# T04_Schematic.net
KiCad netlist of a schematic drawn in EAGLE
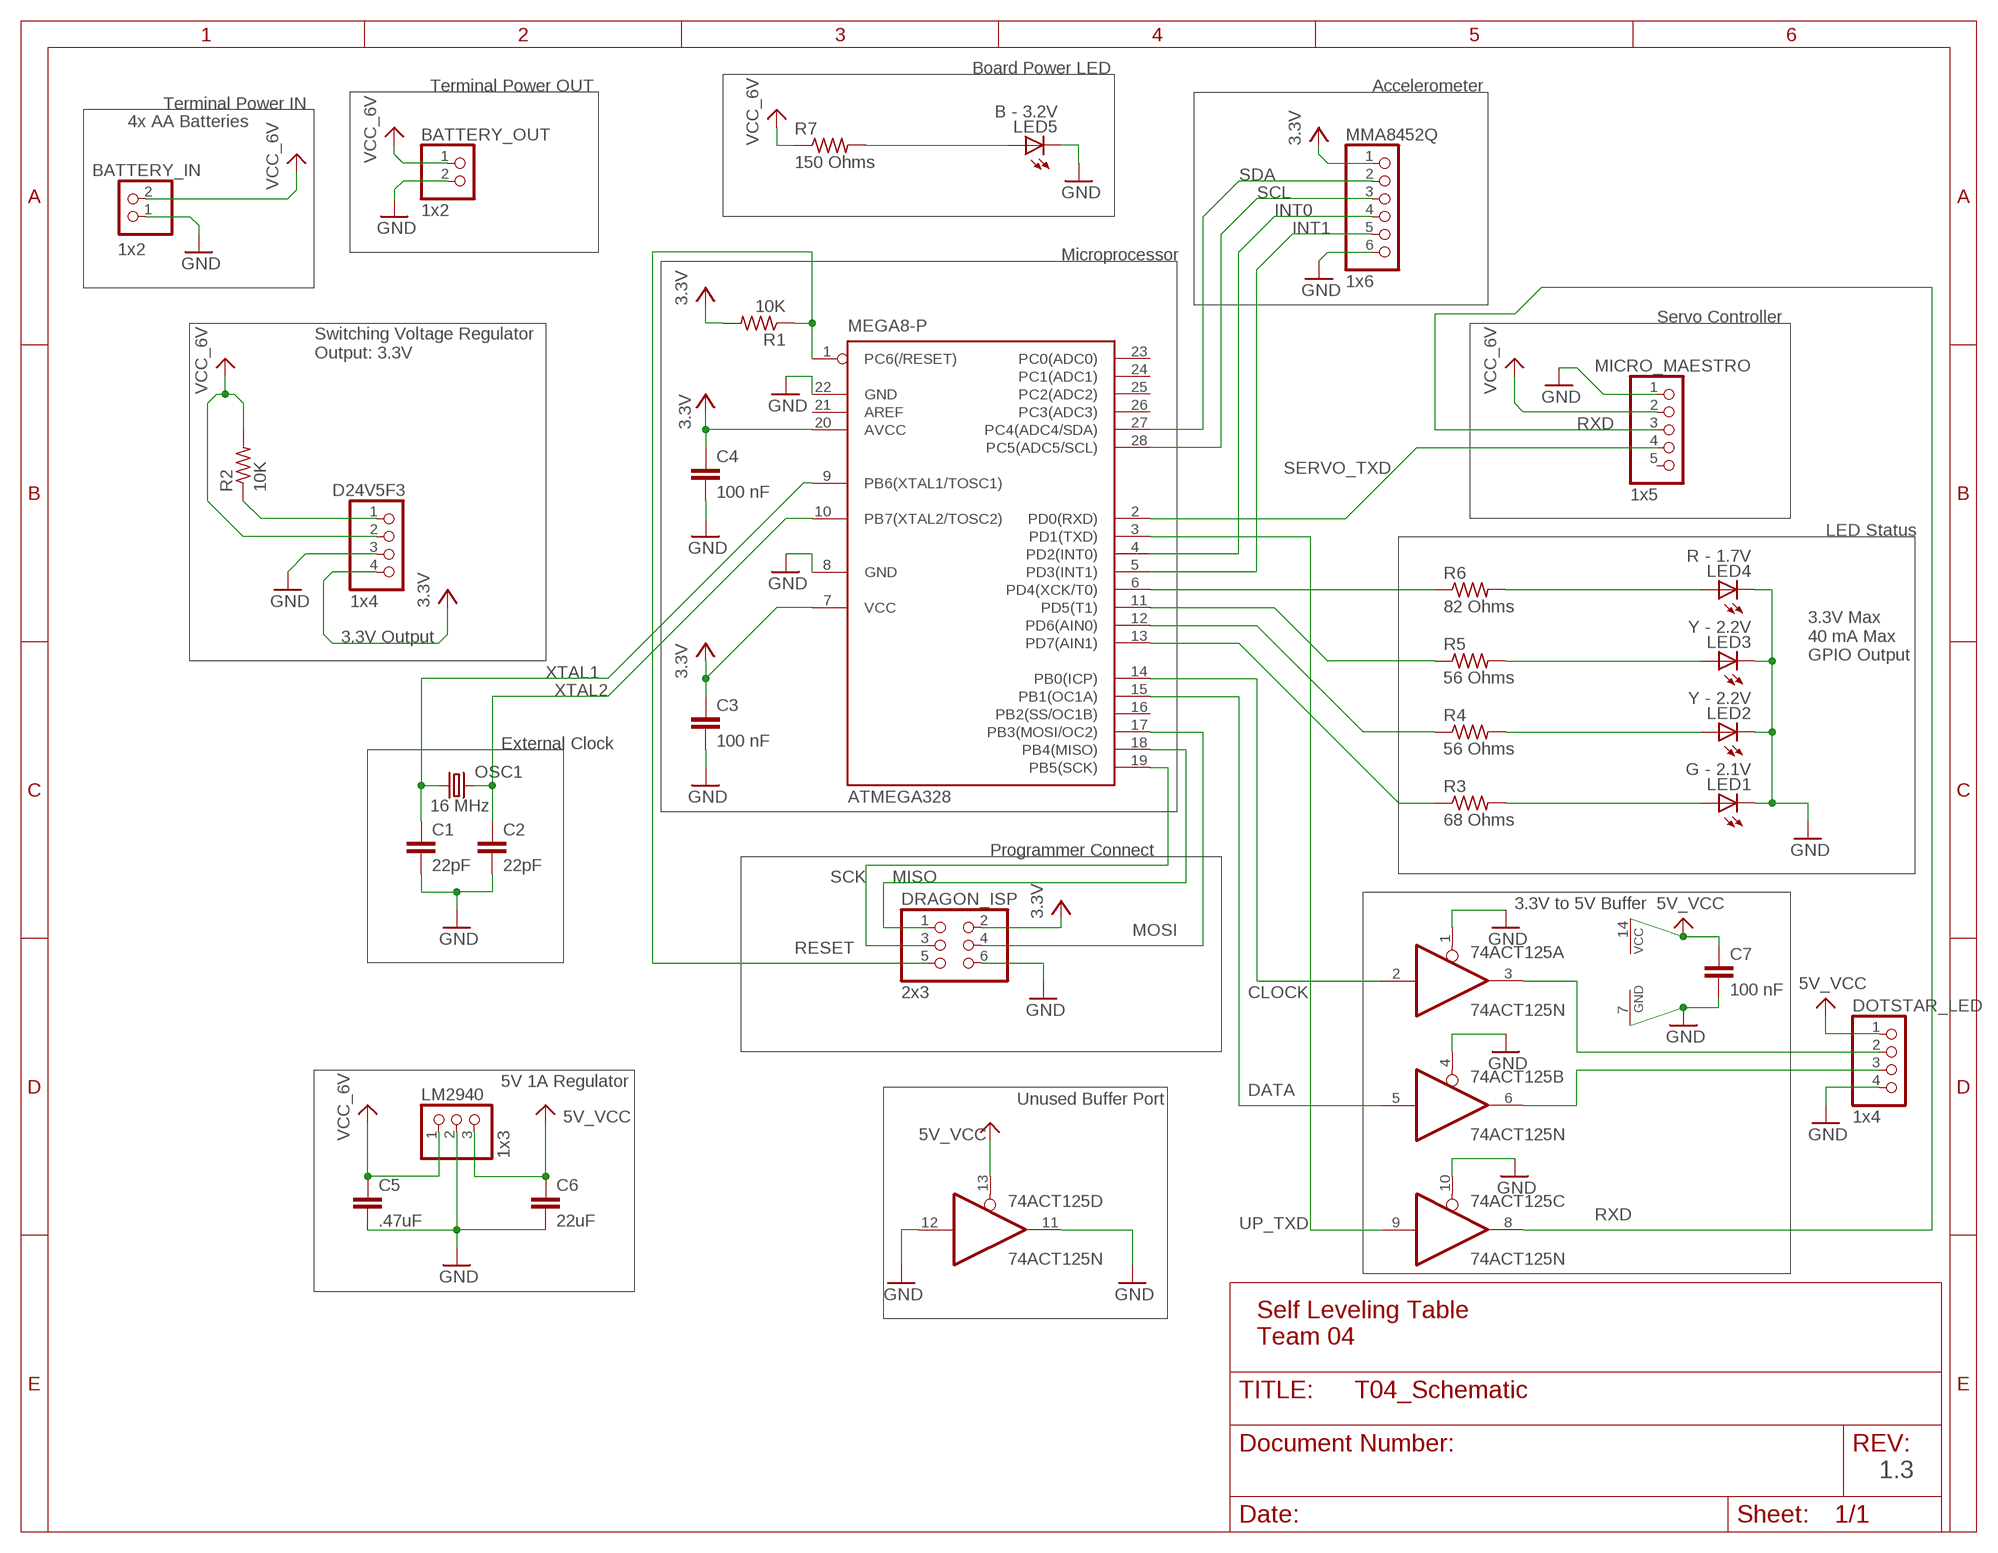
[diagram p0: schematic, sheet 1]

(export (version "E")
  (design (tool "Eeschema 10.0.6"))
  (components
    (comp (ref "74ACT125")
      (value "74ACT125N")
      (footprint "eagle-import:DIL14")
      (libsource (lib "eagle-import") (part "74125NACT"))
    )
    (comp (ref "ATMEGA328")
      (value "MEGA8-P")
      (footprint "eagle-import:DIL28-3")
      (libsource (lib "eagle-import") (part "MEGA8-P"))
    )
    (comp (ref "BATTERY_IN")
      (value "1x2")
      (footprint "eagle-import:1X02")
      (libsource (lib "eagle-import") (part "PINHD-1X2"))
    )
    (comp (ref "BATTERY_OUT")
      (value "1x2")
      (footprint "eagle-import:1X02")
      (libsource (lib "eagle-import") (part "PINHD-1X2"))
    )
    (comp (ref "C1")
      (value "22pF")
      (footprint "eagle-import:C1206")
      (libsource (lib "eagle-import") (part "C-EUC1206"))
    )
    (comp (ref "C2")
      (value "22pF")
      (footprint "eagle-import:C1206")
      (libsource (lib "eagle-import") (part "C-EUC1206"))
    )
    (comp (ref "C3")
      (value "100 nF")
      (footprint "eagle-import:C1206")
      (libsource (lib "eagle-import") (part "C-EUC1206"))
    )
    (comp (ref "C4")
      (value "100 nF")
      (footprint "eagle-import:C1206")
      (libsource (lib "eagle-import") (part "C-EUC1206"))
    )
    (comp (ref "C5")
      (value ".47uF")
      (footprint "eagle-import:C1206")
      (libsource (lib "eagle-import") (part "C-EUC1206"))
    )
    (comp (ref "C6")
      (value "22uF")
      (footprint "eagle-import:C1206")
      (libsource (lib "eagle-import") (part "C-EUC1206"))
    )
    (comp (ref "C7")
      (value "100 nF")
      (footprint "eagle-import:C1206")
      (libsource (lib "eagle-import") (part "C-EUC1206"))
    )
    (comp (ref "D24V5F3")
      (value "1x4")
      (footprint "eagle-import:1X04")
      (libsource (lib "eagle-import") (part "PINHD-1X4"))
    )
    (comp (ref "DOTSTAR_LED")
      (value "1x4")
      (footprint "eagle-import:1X04")
      (libsource (lib "eagle-import") (part "PINHD-1X4"))
    )
    (comp (ref "DRAGON_ISP")
      (value "2x3")
      (footprint "eagle-import:2X03")
      (libsource (lib "eagle-import") (part "PINHD-2X3"))
    )
    (comp (ref "LED1")
      (value "G - 2.1V")
      (footprint "eagle-import:1206")
      (libsource (lib "eagle-import") (part "LEDSMT1206"))
    )
    (comp (ref "LED2")
      (value "Y - 2.2V")
      (footprint "eagle-import:1206")
      (libsource (lib "eagle-import") (part "LEDSMT1206"))
    )
    (comp (ref "LED3")
      (value "Y - 2.2V")
      (footprint "eagle-import:1206")
      (libsource (lib "eagle-import") (part "LEDSMT1206"))
    )
    (comp (ref "LED4")
      (value "R - 1.7V")
      (footprint "eagle-import:1206")
      (libsource (lib "eagle-import") (part "LEDSMT1206"))
    )
    (comp (ref "LED5")
      (value "B - 3.2V")
      (footprint "eagle-import:1206")
      (libsource (lib "eagle-import") (part "LEDSMT1206"))
    )
    (comp (ref "LM2940")
      (value "1x3")
      (footprint "eagle-import:1X03")
      (libsource (lib "eagle-import") (part "PINHD-1X3"))
    )
    (comp (ref "MICRO_MAESTRO")
      (value "1x5")
      (footprint "eagle-import:1X05")
      (libsource (lib "eagle-import") (part "PINHD-1X5"))
    )
    (comp (ref "MMA8452Q")
      (value "1x6")
      (footprint "eagle-import:1X06")
      (libsource (lib "eagle-import") (part "PINHD-1X6"))
    )
    (comp (ref "OSC1")
      (value "16 MHz")
      (footprint "eagle-import:HC49US")
      (libsource (lib "eagle-import") (part "CRYSTALHC49US"))
    )
    (comp (ref "R1")
      (value "10K")
      (footprint "eagle-import:M1206")
      (libsource (lib "eagle-import") (part "R-US_M1206"))
    )
    (comp (ref "R2")
      (value "10K")
      (footprint "eagle-import:M1206")
      (libsource (lib "eagle-import") (part "R-US_M1206"))
    )
    (comp (ref "R3")
      (value "68 Ohms")
      (footprint "eagle-import:R1206")
      (libsource (lib "eagle-import") (part "R-US_R1206"))
    )
    (comp (ref "R4")
      (value "56 Ohms")
      (footprint "eagle-import:R1206")
      (libsource (lib "eagle-import") (part "R-US_R1206"))
    )
    (comp (ref "R5")
      (value "56 Ohms")
      (footprint "eagle-import:R1206")
      (libsource (lib "eagle-import") (part "R-US_R1206"))
    )
    (comp (ref "R6")
      (value "82 Ohms")
      (footprint "eagle-import:R1206")
      (libsource (lib "eagle-import") (part "R-US_R1206"))
    )
    (comp (ref "R7")
      (value "150 Ohms")
      (footprint "eagle-import:R1206")
      (libsource (lib "eagle-import") (part "R-US_R1206"))
    )
  )
  (nets
    (net (code "1") (name "/CLOCK") (class "Default")
      (node (ref "74ACT125") (pin "2") (pinfunction "I_2") (pintype "input"))
      (node (ref "ATMEGA328") (pin "14") (pinfunction "PB0(ICP)_14") (pintype "bidirectional"))
    )
    (net (code "2") (name "/DATA") (class "Default")
      (node (ref "74ACT125") (pin "5") (pinfunction "I_5") (pintype "input"))
      (node (ref "ATMEGA328") (pin "15") (pinfunction "PB1(OC1A)_15") (pintype "bidirectional"))
    )
    (net (code "3") (name "/INT0") (class "Default")
      (node (ref "ATMEGA328") (pin "4") (pinfunction "PD2(INT0)_4") (pintype "bidirectional"))
      (node (ref "MMA8452Q") (pin "4") (pinfunction "4_4") (pintype "passive"))
    )
    (net (code "4") (name "/INT1") (class "Default")
      (node (ref "ATMEGA328") (pin "5") (pinfunction "PD3(INT1)_5") (pintype "bidirectional"))
      (node (ref "MMA8452Q") (pin "5") (pinfunction "5_5") (pintype "passive"))
    )
    (net (code "5") (name "/MISO") (class "Default")
      (node (ref "ATMEGA328") (pin "18") (pinfunction "PB4(MISO)_18") (pintype "bidirectional"))
      (node (ref "DRAGON_ISP") (pin "1") (pinfunction "1_1") (pintype "passive"))
    )
    (net (code "6") (name "/MOSI") (class "Default")
      (node (ref "ATMEGA328") (pin "17") (pinfunction "PB3(MOSI/OC2)_17") (pintype "bidirectional"))
      (node (ref "DRAGON_ISP") (pin "4") (pinfunction "4_4") (pintype "passive"))
    )
    (net (code "7") (name "/RESET") (class "Default")
      (node (ref "ATMEGA328") (pin "1") (pinfunction "PC6(/RESET)_1") (pintype "bidirectional"))
      (node (ref "DRAGON_ISP") (pin "5") (pinfunction "5_5") (pintype "passive"))
      (node (ref "R1") (pin "1") (pinfunction "1_1") (pintype "passive"))
    )
    (net (code "8") (name "/RXD") (class "Default")
      (node (ref "74ACT125") (pin "8") (pinfunction "O_8") (pintype "tri_state"))
      (node (ref "MICRO_MAESTRO") (pin "3") (pinfunction "3_3") (pintype "passive"))
    )
    (net (code "9") (name "/SCK") (class "Default")
      (node (ref "ATMEGA328") (pin "19") (pinfunction "PB5(SCK)_19") (pintype "bidirectional"))
      (node (ref "DRAGON_ISP") (pin "3") (pinfunction "3_3") (pintype "passive"))
    )
    (net (code "10") (name "/SCL") (class "Default")
      (node (ref "ATMEGA328") (pin "28") (pinfunction "PC5(ADC5/SCL)_28") (pintype "bidirectional"))
      (node (ref "MMA8452Q") (pin "3") (pinfunction "3_3") (pintype "passive"))
    )
    (net (code "11") (name "/SDA") (class "Default")
      (node (ref "ATMEGA328") (pin "27") (pinfunction "PC4(ADC4/SDA)_27") (pintype "bidirectional"))
      (node (ref "MMA8452Q") (pin "2") (pinfunction "2_2") (pintype "passive"))
    )
    (net (code "12") (name "/SERVO_TXD") (class "Default")
      (node (ref "ATMEGA328") (pin "2") (pinfunction "PD0(RXD)_2") (pintype "bidirectional"))
      (node (ref "MICRO_MAESTRO") (pin "4") (pinfunction "4_4") (pintype "passive"))
    )
    (net (code "13") (name "/UP_TXD") (class "Default")
      (node (ref "74ACT125") (pin "9") (pinfunction "I_9") (pintype "input"))
      (node (ref "ATMEGA328") (pin "3") (pinfunction "PD1(TXD)_3") (pintype "bidirectional"))
    )
    (net (code "14") (name "/XTAL1") (class "Default")
      (node (ref "ATMEGA328") (pin "9") (pinfunction "PB6(XTAL1/TOSC1)_9") (pintype "bidirectional"))
      (node (ref "C1") (pin "1") (pinfunction "1_1") (pintype "passive"))
      (node (ref "OSC1") (pin "1") (pinfunction "1_1") (pintype "passive"))
    )
    (net (code "15") (name "/XTAL2") (class "Default")
      (node (ref "ATMEGA328") (pin "10") (pinfunction "PB7(XTAL2/TOSC2)_10") (pintype "bidirectional"))
      (node (ref "C2") (pin "1") (pinfunction "1_1") (pintype "passive"))
      (node (ref "OSC1") (pin "2") (pinfunction "2_2") (pintype "passive"))
    )
    (net (code "16") (name "3.3V") (class "Default")
      (node (ref "ATMEGA328") (pin "20") (pinfunction "AVCC_20") (pintype "power_in"))
      (node (ref "ATMEGA328") (pin "7") (pinfunction "VCC_7") (pintype "power_in"))
      (node (ref "C3") (pin "1") (pinfunction "1_1") (pintype "passive"))
      (node (ref "C4") (pin "1") (pinfunction "1_1") (pintype "passive"))
      (node (ref "D24V5F3") (pin "4") (pinfunction "4_4") (pintype "passive"))
      (node (ref "DRAGON_ISP") (pin "2") (pinfunction "2_2") (pintype "passive"))
      (node (ref "MMA8452Q") (pin "1") (pinfunction "1_1") (pintype "passive"))
      (node (ref "R1") (pin "2") (pinfunction "2_2") (pintype "passive"))
    )
    (net (code "17") (name "5V_VCC") (class "Default")
      (node (ref "74ACT125") (pin "13") (pinfunction "OE_13") (pintype "input"))
      (node (ref "74ACT125") (pin "14") (pinfunction "VCC_14") (pintype "power_in"))
      (node (ref "C6") (pin "1") (pinfunction "1_1") (pintype "passive"))
      (node (ref "C7") (pin "1") (pinfunction "1_1") (pintype "passive"))
      (node (ref "DOTSTAR_LED") (pin "1") (pinfunction "1_1") (pintype "passive"))
      (node (ref "LM2940") (pin "3") (pinfunction "3_3") (pintype "passive"))
    )
    (net (code "18") (name "GND") (class "Default")
      (node (ref "74ACT125") (pin "1") (pinfunction "OE_1") (pintype "input"))
      (node (ref "74ACT125") (pin "10") (pinfunction "OE_10") (pintype "input"))
      (node (ref "74ACT125") (pin "11") (pinfunction "O_11") (pintype "tri_state"))
      (node (ref "74ACT125") (pin "12") (pinfunction "I_12") (pintype "input"))
      (node (ref "74ACT125") (pin "4") (pinfunction "OE_4") (pintype "input"))
      (node (ref "74ACT125") (pin "7") (pinfunction "GND_7") (pintype "power_in"))
      (node (ref "ATMEGA328") (pin "22") (pinfunction "GND_22") (pintype "power_in"))
      (node (ref "ATMEGA328") (pin "8") (pinfunction "GND_8") (pintype "power_in"))
      (node (ref "BATTERY_IN") (pin "1") (pinfunction "1_1") (pintype "passive"))
      (node (ref "BATTERY_OUT") (pin "2") (pinfunction "2_2") (pintype "passive"))
      (node (ref "C1") (pin "2") (pinfunction "2_2") (pintype "passive"))
      (node (ref "C2") (pin "2") (pinfunction "2_2") (pintype "passive"))
      (node (ref "C3") (pin "2") (pinfunction "2_2") (pintype "passive"))
      (node (ref "C4") (pin "2") (pinfunction "2_2") (pintype "passive"))
      (node (ref "C5") (pin "2") (pinfunction "2_2") (pintype "passive"))
      (node (ref "C6") (pin "2") (pinfunction "2_2") (pintype "passive"))
      (node (ref "C7") (pin "2") (pinfunction "2_2") (pintype "passive"))
      (node (ref "D24V5F3") (pin "3") (pinfunction "3_3") (pintype "passive"))
      (node (ref "DOTSTAR_LED") (pin "4") (pinfunction "4_4") (pintype "passive"))
      (node (ref "DRAGON_ISP") (pin "6") (pinfunction "6_6") (pintype "passive"))
      (node (ref "LED1") (pin "C") (pinfunction "C_C") (pintype "passive"))
      (node (ref "LED2") (pin "C") (pinfunction "C_C") (pintype "passive"))
      (node (ref "LED3") (pin "C") (pinfunction "C_C") (pintype "passive"))
      (node (ref "LED4") (pin "C") (pinfunction "C_C") (pintype "passive"))
      (node (ref "LED5") (pin "C") (pinfunction "C_C") (pintype "passive"))
      (node (ref "LM2940") (pin "2") (pinfunction "2_2") (pintype "passive"))
      (node (ref "MICRO_MAESTRO") (pin "1") (pinfunction "1_1") (pintype "passive"))
      (node (ref "MMA8452Q") (pin "6") (pinfunction "6_6") (pintype "passive"))
    )
    (net (code "19") (name "Net-(74ACT125A-O)") (class "Default")
      (node (ref "74ACT125") (pin "3") (pinfunction "O_3") (pintype "tri_state"))
      (node (ref "DOTSTAR_LED") (pin "2") (pinfunction "2_2") (pintype "passive"))
    )
    (net (code "20") (name "Net-(74ACT125B-O)") (class "Default")
      (node (ref "74ACT125") (pin "6") (pinfunction "O_6") (pintype "tri_state"))
      (node (ref "DOTSTAR_LED") (pin "3") (pinfunction "3_3") (pintype "passive"))
    )
    (net (code "21") (name "Net-(ATMEGA328-PD4(XCK{slash}T0))") (class "Default")
      (node (ref "ATMEGA328") (pin "6") (pinfunction "PD4(XCK/T0)_6") (pintype "bidirectional"))
      (node (ref "R6") (pin "1") (pinfunction "1_1") (pintype "passive"))
    )
    (net (code "22") (name "Net-(ATMEGA328-PD5(T1))") (class "Default")
      (node (ref "ATMEGA328") (pin "11") (pinfunction "PD5(T1)_11") (pintype "bidirectional"))
      (node (ref "R5") (pin "1") (pinfunction "1_1") (pintype "passive"))
    )
    (net (code "23") (name "Net-(ATMEGA328-PD6(AIN0))") (class "Default")
      (node (ref "ATMEGA328") (pin "12") (pinfunction "PD6(AIN0)_12") (pintype "bidirectional"))
      (node (ref "R4") (pin "1") (pinfunction "1_1") (pintype "passive"))
    )
    (net (code "24") (name "Net-(ATMEGA328-PD7(AIN1))") (class "Default")
      (node (ref "ATMEGA328") (pin "13") (pinfunction "PD7(AIN1)_13") (pintype "bidirectional"))
      (node (ref "R3") (pin "1") (pinfunction "1_1") (pintype "passive"))
    )
    (net (code "25") (name "Net-(D24V5F3-Pad1)") (class "Default")
      (node (ref "D24V5F3") (pin "1") (pinfunction "1_1") (pintype "passive"))
      (node (ref "R2") (pin "1") (pinfunction "1_1") (pintype "passive"))
    )
    (net (code "26") (name "Net-(LED1-PadA)") (class "Default")
      (node (ref "LED1") (pin "A") (pinfunction "A_A") (pintype "passive"))
      (node (ref "R3") (pin "2") (pinfunction "2_2") (pintype "passive"))
    )
    (net (code "27") (name "Net-(LED2-PadA)") (class "Default")
      (node (ref "LED2") (pin "A") (pinfunction "A_A") (pintype "passive"))
      (node (ref "R4") (pin "2") (pinfunction "2_2") (pintype "passive"))
    )
    (net (code "28") (name "Net-(LED3-PadA)") (class "Default")
      (node (ref "LED3") (pin "A") (pinfunction "A_A") (pintype "passive"))
      (node (ref "R5") (pin "2") (pinfunction "2_2") (pintype "passive"))
    )
    (net (code "29") (name "Net-(LED4-PadA)") (class "Default")
      (node (ref "LED4") (pin "A") (pinfunction "A_A") (pintype "passive"))
      (node (ref "R6") (pin "2") (pinfunction "2_2") (pintype "passive"))
    )
    (net (code "30") (name "Net-(LED5-PadA)") (class "Default")
      (node (ref "LED5") (pin "A") (pinfunction "A_A") (pintype "passive"))
      (node (ref "R7") (pin "2") (pinfunction "2_2") (pintype "passive"))
    )
    (net (code "31") (name "VCC_6V") (class "Default")
      (node (ref "BATTERY_IN") (pin "2") (pinfunction "2_2") (pintype "passive"))
      (node (ref "BATTERY_OUT") (pin "1") (pinfunction "1_1") (pintype "passive"))
      (node (ref "C5") (pin "1") (pinfunction "1_1") (pintype "passive"))
      (node (ref "D24V5F3") (pin "2") (pinfunction "2_2") (pintype "passive"))
      (node (ref "LM2940") (pin "1") (pinfunction "1_1") (pintype "passive"))
      (node (ref "MICRO_MAESTRO") (pin "2") (pinfunction "2_2") (pintype "passive"))
      (node (ref "R2") (pin "2") (pinfunction "2_2") (pintype "passive"))
      (node (ref "R7") (pin "1") (pinfunction "1_1") (pintype "passive"))
    )
    (net (code "32") (name "unconnected-(ATMEGA328-AREF-Pad21)") (class "Default")
      (node (ref "ATMEGA328") (pin "21") (pinfunction "AREF_21") (pintype "passive"))
    )
    (net (code "33") (name "unconnected-(ATMEGA328-PB2(SS{slash}OC1B)-Pad16)") (class "Default")
      (node (ref "ATMEGA328") (pin "16") (pinfunction "PB2(SS/OC1B)_16") (pintype "bidirectional"))
    )
    (net (code "34") (name "unconnected-(ATMEGA328-PC0(ADC0)-Pad23)") (class "Default")
      (node (ref "ATMEGA328") (pin "23") (pinfunction "PC0(ADC0)_23") (pintype "bidirectional"))
    )
    (net (code "35") (name "unconnected-(ATMEGA328-PC1(ADC1)-Pad24)") (class "Default")
      (node (ref "ATMEGA328") (pin "24") (pinfunction "PC1(ADC1)_24") (pintype "bidirectional"))
    )
    (net (code "36") (name "unconnected-(ATMEGA328-PC2(ADC2)-Pad25)") (class "Default")
      (node (ref "ATMEGA328") (pin "25") (pinfunction "PC2(ADC2)_25") (pintype "bidirectional"))
    )
    (net (code "37") (name "unconnected-(ATMEGA328-PC3(ADC3)-Pad26)") (class "Default")
      (node (ref "ATMEGA328") (pin "26") (pinfunction "PC3(ADC3)_26") (pintype "bidirectional"))
    )
    (net (code "38") (name "unconnected-(MICRO_MAESTRO-Pad5)") (class "Default")
      (node (ref "MICRO_MAESTRO") (pin "5") (pinfunction "5_5") (pintype "passive"))
    )
  )
)
